# ZynqPower.net
KiCad netlist of a schematic drawn in Altium Designer
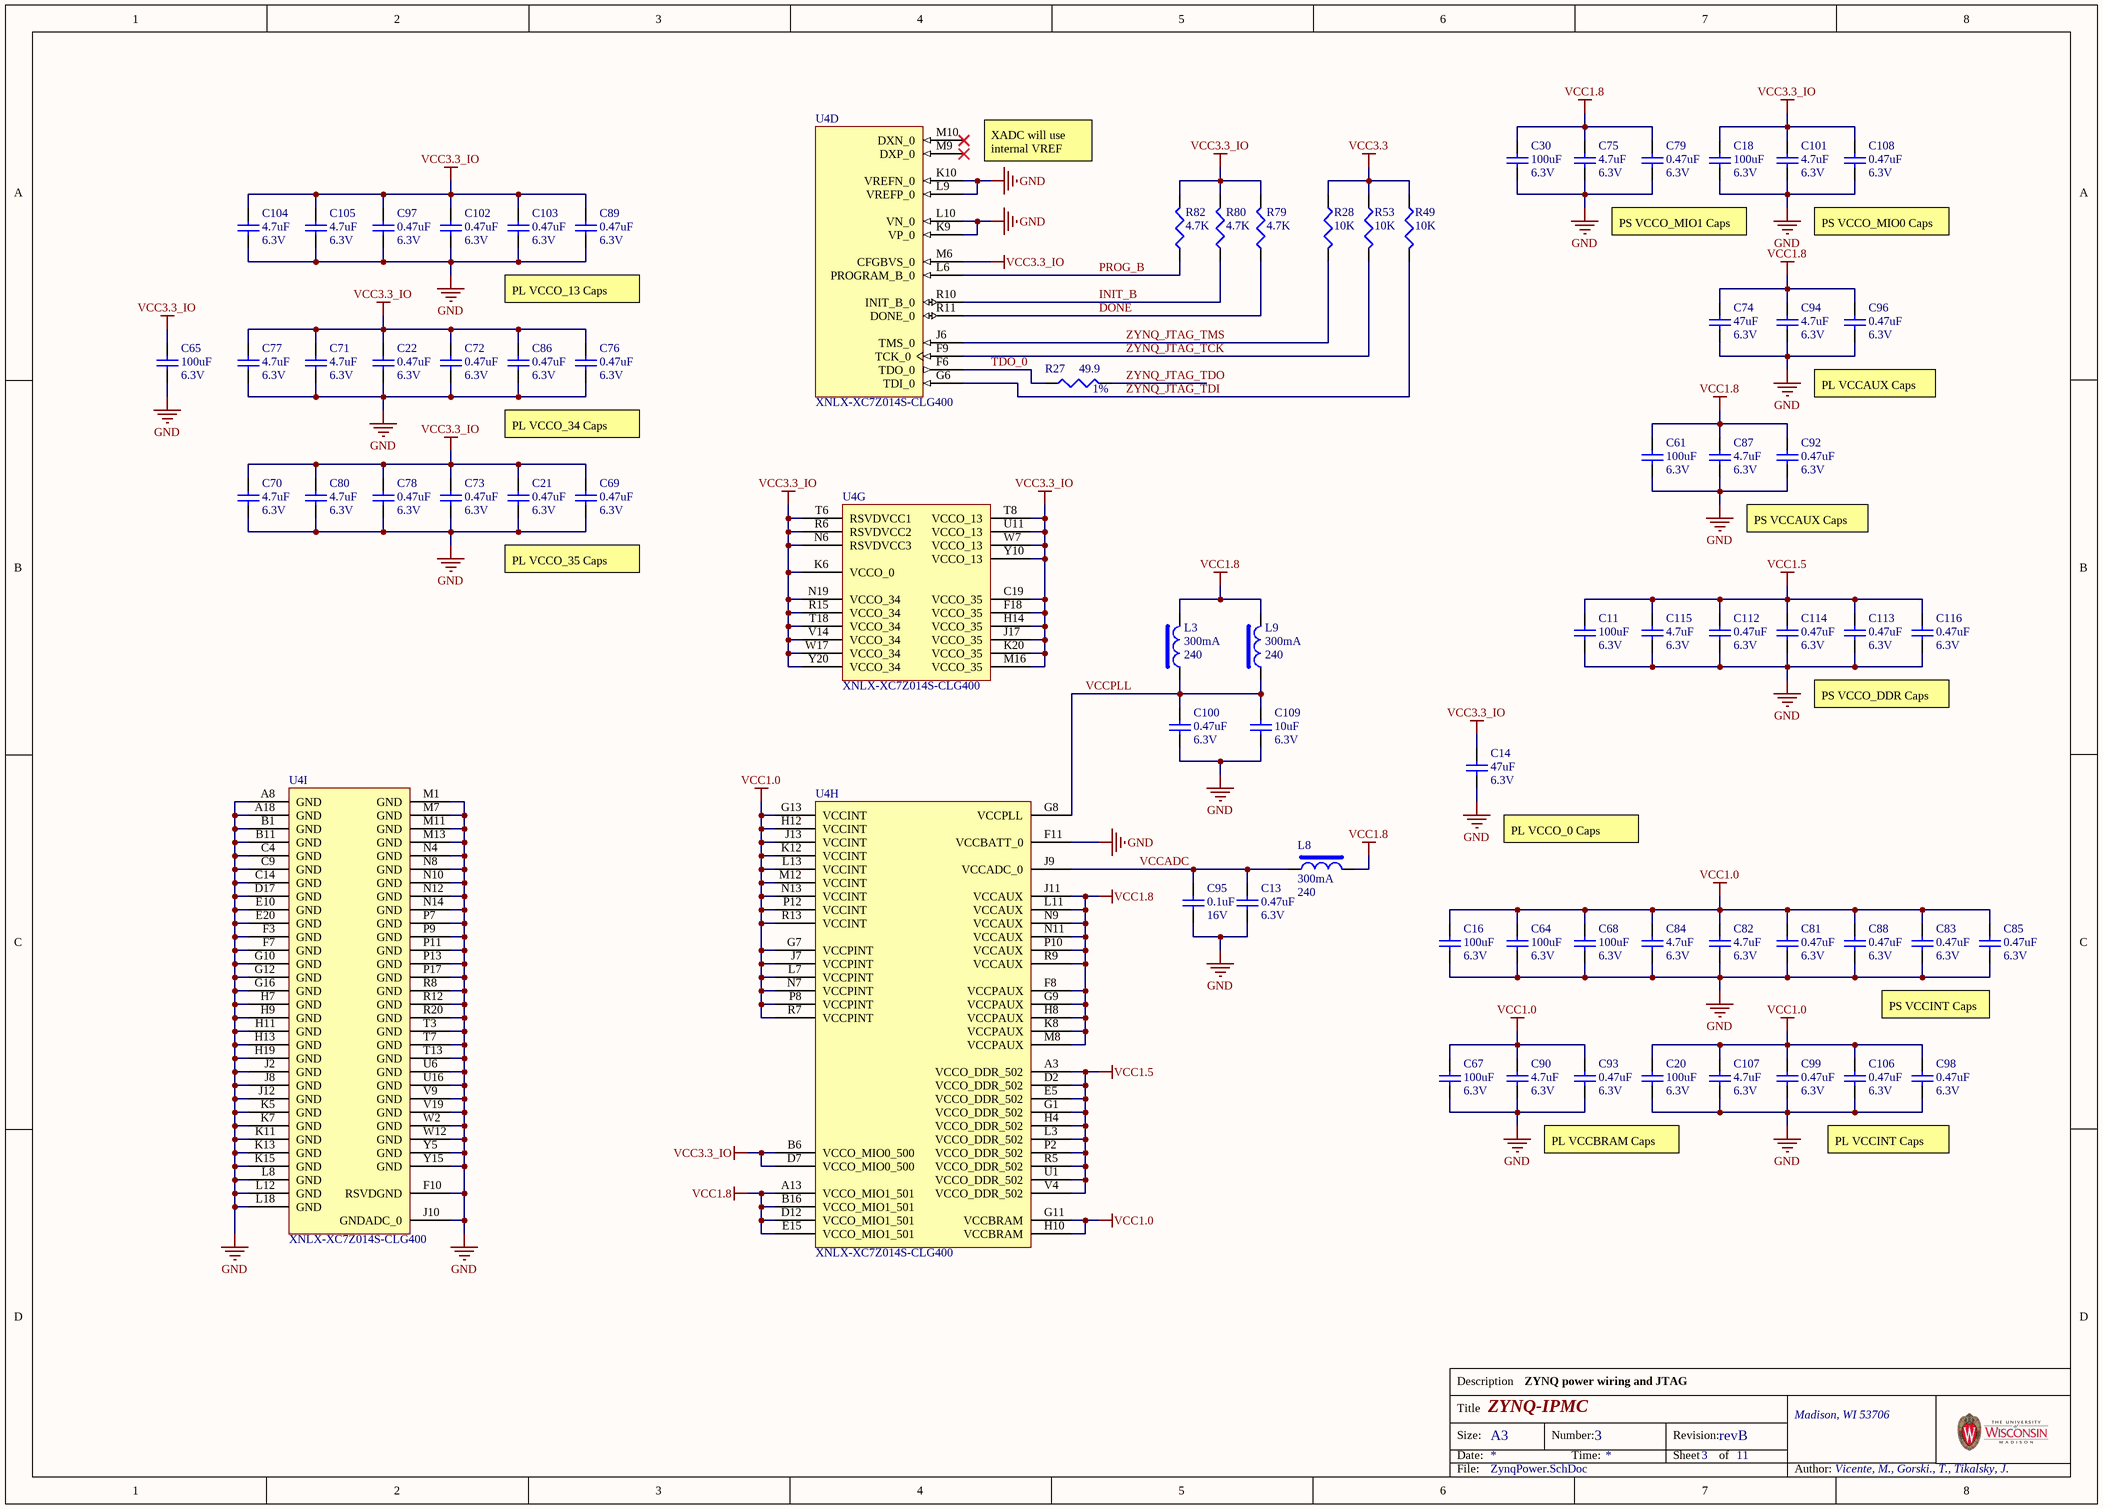
[diagram p0: ZynqPower.SchDoc]

(export (version "E")
  (design (tool "Eeschema 10.0.6"))
  (components
    (comp (ref "C11")
      (value "100uF")
      (footprint "C1210_IPC_H")
      (description "Capacitor")
      (fields
        (field (name "RATING") "6.3V")
        (field (name "PART") "GRM32ER60J107ME20L")
        (field (name "MANUFACTURER") "Murata")
      )
      (libsource (lib "CustomParts") (part "Cap"))
    )
    (comp (ref "C13")
      (value "0.47uF")
      (footprint "C0402_IPC_H")
      (description "Capacitor")
      (fields
        (field (name "RATING") "6.3V")
        (field (name "MANUFACTURER") "Murata")
        (field (name "PART") "GRM155R60J474KE19D")
      )
      (libsource (lib "CustomParts") (part "Cap"))
    )
    (comp (ref "C14")
      (value "47uF")
      (footprint "C0805_M")
      (description "Capacitor")
      (fields
        (field (name "RATING") "6.3V")
        (field (name "MANUFACTURER") "TDK")
        (field (name "PART") "C2012X5R0J476M125AC")
      )
      (libsource (lib "CustomParts") (part "Cap"))
    )
    (comp (ref "C16")
      (value "100uF")
      (footprint "C1210_IPC_H")
      (description "Capacitor")
      (fields
        (field (name "RATING") "6.3V")
        (field (name "PART") "GRM32ER60J107ME20L")
        (field (name "MANUFACTURER") "Murata")
      )
      (libsource (lib "CustomParts") (part "Cap"))
    )
    (comp (ref "C18")
      (value "100uF")
      (footprint "C1210_IPC_H")
      (description "Capacitor")
      (fields
        (field (name "RATING") "6.3V")
        (field (name "PART") "GRM32ER60J107ME20L")
        (field (name "MANUFACTURER") "Murata")
      )
      (libsource (lib "CustomParts") (part "Cap"))
    )
    (comp (ref "C20")
      (value "100uF")
      (footprint "C1210_IPC_H")
      (description "Capacitor")
      (fields
        (field (name "RATING") "6.3V")
        (field (name "PART") "GRM32ER60J107ME20L")
        (field (name "MANUFACTURER") "Murata")
      )
      (libsource (lib "CustomParts") (part "Cap"))
    )
    (comp (ref "C21")
      (value "0.47uF")
      (footprint "C0402_IPC_H")
      (description "Capacitor")
      (fields
        (field (name "RATING") "6.3V")
        (field (name "MANUFACTURER") "Murata")
        (field (name "PART") "GRM155R60J474KE19D")
      )
      (libsource (lib "CustomParts") (part "Cap"))
    )
    (comp (ref "C22")
      (value "0.47uF")
      (footprint "C0402_IPC_H")
      (description "Capacitor")
      (fields
        (field (name "RATING") "6.3V")
        (field (name "MANUFACTURER") "Murata")
        (field (name "PART") "GRM155R60J474KE19D")
      )
      (libsource (lib "CustomParts") (part "Cap"))
    )
    (comp (ref "C30")
      (value "100uF")
      (footprint "C1210_IPC_H")
      (description "Capacitor")
      (fields
        (field (name "RATING") "6.3V")
        (field (name "PART") "GRM32ER60J107ME20L")
        (field (name "MANUFACTURER") "Murata")
      )
      (libsource (lib "CustomParts") (part "Cap"))
    )
    (comp (ref "C61")
      (value "100uF")
      (footprint "C1210_IPC_H")
      (description "Capacitor")
      (fields
        (field (name "RATING") "6.3V")
        (field (name "PART") "GRM32ER60J107ME20L")
        (field (name "MANUFACTURER") "Murata")
      )
      (libsource (lib "CustomParts") (part "Cap"))
    )
    (comp (ref "C64")
      (value "100uF")
      (footprint "C1210_IPC_H")
      (description "Capacitor")
      (fields
        (field (name "RATING") "6.3V")
        (field (name "PART") "GRM32ER60J107ME20L")
        (field (name "MANUFACTURER") "Murata")
      )
      (libsource (lib "CustomParts") (part "Cap"))
    )
    (comp (ref "C65")
      (value "100uF")
      (footprint "C1210_IPC_H")
      (description "Capacitor")
      (fields
        (field (name "RATING") "6.3V")
        (field (name "PART") "GRM32ER60J107ME20L")
        (field (name "MANUFACTURER") "Murata")
      )
      (libsource (lib "CustomParts") (part "Cap"))
    )
    (comp (ref "C67")
      (value "100uF")
      (footprint "C1210_IPC_H")
      (description "Capacitor")
      (fields
        (field (name "RATING") "6.3V")
        (field (name "PART") "GRM32ER60J107ME20L")
        (field (name "MANUFACTURER") "Murata")
      )
      (libsource (lib "CustomParts") (part "Cap"))
    )
    (comp (ref "C68")
      (value "100uF")
      (footprint "C1210_IPC_H")
      (description "Capacitor")
      (fields
        (field (name "RATING") "6.3V")
        (field (name "PART") "GRM32ER60J107ME20L")
        (field (name "MANUFACTURER") "Murata")
      )
      (libsource (lib "CustomParts") (part "Cap"))
    )
    (comp (ref "C69")
      (value "0.47uF")
      (footprint "C0402_IPC_H")
      (description "Capacitor")
      (fields
        (field (name "RATING") "6.3V")
        (field (name "MANUFACTURER") "Murata")
        (field (name "PART") "GRM155R60J474KE19D")
      )
      (libsource (lib "CustomParts") (part "Cap"))
    )
    (comp (ref "C70")
      (value "4.7uF")
      (footprint "C0402_IPC_H")
      (description "Capacitor")
      (fields
        (field (name "RATING") "6.3V")
        (field (name "MANUFACTURER") "TDK")
        (field (name "PART") "C1005X5R0J475M050BC")
      )
      (libsource (lib "CustomParts") (part "Cap"))
    )
    (comp (ref "C71")
      (value "4.7uF")
      (footprint "C0402_IPC_H")
      (description "Capacitor")
      (fields
        (field (name "RATING") "6.3V")
        (field (name "MANUFACTURER") "TDK")
        (field (name "PART") "C1005X5R0J475M050BC")
      )
      (libsource (lib "CustomParts") (part "Cap"))
    )
    (comp (ref "C72")
      (value "0.47uF")
      (footprint "C0402_IPC_H")
      (description "Capacitor")
      (fields
        (field (name "RATING") "6.3V")
        (field (name "MANUFACTURER") "Murata")
        (field (name "PART") "GRM155R60J474KE19D")
      )
      (libsource (lib "CustomParts") (part "Cap"))
    )
    (comp (ref "C73")
      (value "0.47uF")
      (footprint "C0402_IPC_H")
      (description "Capacitor")
      (fields
        (field (name "RATING") "6.3V")
        (field (name "MANUFACTURER") "Murata")
        (field (name "PART") "GRM155R60J474KE19D")
      )
      (libsource (lib "CustomParts") (part "Cap"))
    )
    (comp (ref "C74")
      (value "47uF")
      (footprint "C0805_M")
      (description "Capacitor")
      (fields
        (field (name "RATING") "6.3V")
        (field (name "MANUFACTURER") "TDK")
        (field (name "PART") "C2012X5R0J476M125AC")
      )
      (libsource (lib "CustomParts") (part "Cap"))
    )
    (comp (ref "C75")
      (value "4.7uF")
      (footprint "C0402_IPC_H")
      (description "Capacitor")
      (fields
        (field (name "RATING") "6.3V")
        (field (name "MANUFACTURER") "TDK")
        (field (name "PART") "C1005X5R0J475M050BC")
      )
      (libsource (lib "CustomParts") (part "Cap"))
    )
    (comp (ref "C76")
      (value "0.47uF")
      (footprint "C0402_IPC_H")
      (description "Capacitor")
      (fields
        (field (name "RATING") "6.3V")
        (field (name "MANUFACTURER") "Murata")
        (field (name "PART") "GRM155R60J474KE19D")
      )
      (libsource (lib "CustomParts") (part "Cap"))
    )
    (comp (ref "C77")
      (value "4.7uF")
      (footprint "C0402_IPC_H")
      (description "Capacitor")
      (fields
        (field (name "RATING") "6.3V")
        (field (name "MANUFACTURER") "TDK")
        (field (name "PART") "C1005X5R0J475M050BC")
      )
      (libsource (lib "CustomParts") (part "Cap"))
    )
    (comp (ref "C78")
      (value "0.47uF")
      (footprint "C0402_IPC_H")
      (description "Capacitor")
      (fields
        (field (name "RATING") "6.3V")
        (field (name "MANUFACTURER") "Murata")
        (field (name "PART") "GRM155R60J474KE19D")
      )
      (libsource (lib "CustomParts") (part "Cap"))
    )
    (comp (ref "C79")
      (value "0.47uF")
      (footprint "C0402_IPC_H")
      (description "Capacitor")
      (fields
        (field (name "RATING") "6.3V")
        (field (name "MANUFACTURER") "Murata")
        (field (name "PART") "GRM155R60J474KE19D")
      )
      (libsource (lib "CustomParts") (part "Cap"))
    )
    (comp (ref "C80")
      (value "4.7uF")
      (footprint "C0402_IPC_H")
      (description "Capacitor")
      (fields
        (field (name "RATING") "6.3V")
        (field (name "MANUFACTURER") "TDK")
        (field (name "PART") "C1005X5R0J475M050BC")
      )
      (libsource (lib "CustomParts") (part "Cap"))
    )
    (comp (ref "C81")
      (value "0.47uF")
      (footprint "C0402_IPC_H")
      (description "Capacitor")
      (fields
        (field (name "RATING") "6.3V")
        (field (name "MANUFACTURER") "Murata")
        (field (name "PART") "GRM155R60J474KE19D")
      )
      (libsource (lib "CustomParts") (part "Cap"))
    )
    (comp (ref "C82")
      (value "4.7uF")
      (footprint "C0402_IPC_H")
      (description "Capacitor")
      (fields
        (field (name "RATING") "6.3V")
        (field (name "MANUFACTURER") "TDK")
        (field (name "PART") "C1005X5R0J475M050BC")
      )
      (libsource (lib "CustomParts") (part "Cap"))
    )
    (comp (ref "C83")
      (value "0.47uF")
      (footprint "C0402_IPC_H")
      (description "Capacitor")
      (fields
        (field (name "RATING") "6.3V")
        (field (name "MANUFACTURER") "Murata")
        (field (name "PART") "GRM155R60J474KE19D")
      )
      (libsource (lib "CustomParts") (part "Cap"))
    )
    (comp (ref "C84")
      (value "4.7uF")
      (footprint "C0402_IPC_H")
      (description "Capacitor")
      (fields
        (field (name "RATING") "6.3V")
        (field (name "MANUFACTURER") "TDK")
        (field (name "PART") "C1005X5R0J475M050BC")
      )
      (libsource (lib "CustomParts") (part "Cap"))
    )
    (comp (ref "C85")
      (value "0.47uF")
      (footprint "C0402_IPC_H")
      (description "Capacitor")
      (fields
        (field (name "RATING") "6.3V")
        (field (name "MANUFACTURER") "Murata")
        (field (name "PART") "GRM155R60J474KE19D")
      )
      (libsource (lib "CustomParts") (part "Cap"))
    )
    (comp (ref "C86")
      (value "0.47uF")
      (footprint "C0402_IPC_H")
      (description "Capacitor")
      (fields
        (field (name "RATING") "6.3V")
        (field (name "MANUFACTURER") "Murata")
        (field (name "PART") "GRM155R60J474KE19D")
      )
      (libsource (lib "CustomParts") (part "Cap"))
    )
    (comp (ref "C87")
      (value "4.7uF")
      (footprint "C0402_IPC_H")
      (description "Capacitor")
      (fields
        (field (name "RATING") "6.3V")
        (field (name "MANUFACTURER") "TDK")
        (field (name "PART") "C1005X5R0J475M050BC")
      )
      (libsource (lib "CustomParts") (part "Cap"))
    )
    (comp (ref "C88")
      (value "0.47uF")
      (footprint "C0402_IPC_H")
      (description "Capacitor")
      (fields
        (field (name "RATING") "6.3V")
        (field (name "MANUFACTURER") "Murata")
        (field (name "PART") "GRM155R60J474KE19D")
      )
      (libsource (lib "CustomParts") (part "Cap"))
    )
    (comp (ref "C89")
      (value "0.47uF")
      (footprint "C0402_IPC_H")
      (description "Capacitor")
      (fields
        (field (name "RATING") "6.3V")
        (field (name "MANUFACTURER") "Murata")
        (field (name "PART") "GRM155R60J474KE19D")
      )
      (libsource (lib "CustomParts") (part "Cap"))
    )
    (comp (ref "C90")
      (value "4.7uF")
      (footprint "C0402_IPC_H")
      (description "Capacitor")
      (fields
        (field (name "RATING") "6.3V")
        (field (name "MANUFACTURER") "TDK")
        (field (name "PART") "C1005X5R0J475M050BC")
      )
      (libsource (lib "CustomParts") (part "Cap"))
    )
    (comp (ref "C92")
      (value "0.47uF")
      (footprint "C0402_IPC_H")
      (description "Capacitor")
      (fields
        (field (name "RATING") "6.3V")
        (field (name "MANUFACTURER") "Murata")
        (field (name "PART") "GRM155R60J474KE19D")
      )
      (libsource (lib "CustomParts") (part "Cap"))
    )
    (comp (ref "C93")
      (value "0.47uF")
      (footprint "C0402_IPC_H")
      (description "Capacitor")
      (fields
        (field (name "RATING") "6.3V")
        (field (name "MANUFACTURER") "Murata")
        (field (name "PART") "GRM155R60J474KE19D")
      )
      (libsource (lib "CustomParts") (part "Cap"))
    )
    (comp (ref "C94")
      (value "4.7uF")
      (footprint "C0402_IPC_H")
      (description "Capacitor")
      (fields
        (field (name "RATING") "6.3V")
        (field (name "MANUFACTURER") "TDK")
        (field (name "PART") "C1005X5R0J475M050BC")
      )
      (libsource (lib "CustomParts") (part "Cap"))
    )
    (comp (ref "C95")
      (value "0.1uF")
      (footprint "C0402_IPC_H")
      (description "Capacitor")
      (fields
        (field (name "RATING") "16V")
        (field (name "MANUFACTURER") "Murata")
        (field (name "PART") "GRM155R71C104KA88D")
      )
      (libsource (lib "CustomParts") (part "Cap"))
    )
    (comp (ref "C96")
      (value "0.47uF")
      (footprint "C0402_IPC_H")
      (description "Capacitor")
      (fields
        (field (name "RATING") "6.3V")
        (field (name "MANUFACTURER") "Murata")
        (field (name "PART") "GRM155R60J474KE19D")
      )
      (libsource (lib "CustomParts") (part "Cap"))
    )
    (comp (ref "C97")
      (value "0.47uF")
      (footprint "C0402_IPC_H")
      (description "Capacitor")
      (fields
        (field (name "RATING") "6.3V")
        (field (name "MANUFACTURER") "Murata")
        (field (name "PART") "GRM155R60J474KE19D")
      )
      (libsource (lib "CustomParts") (part "Cap"))
    )
    (comp (ref "C98")
      (value "0.47uF")
      (footprint "C0402_IPC_H")
      (description "Capacitor")
      (fields
        (field (name "RATING") "6.3V")
        (field (name "MANUFACTURER") "Murata")
        (field (name "PART") "GRM155R60J474KE19D")
      )
      (libsource (lib "CustomParts") (part "Cap"))
    )
    (comp (ref "C99")
      (value "0.47uF")
      (footprint "C0402_IPC_H")
      (description "Capacitor")
      (fields
        (field (name "RATING") "6.3V")
        (field (name "MANUFACTURER") "Murata")
        (field (name "PART") "GRM155R60J474KE19D")
      )
      (libsource (lib "CustomParts") (part "Cap"))
    )
    (comp (ref "C100")
      (value "0.47uF")
      (footprint "C0402_IPC_H")
      (description "Capacitor")
      (fields
        (field (name "RATING") "6.3V")
        (field (name "MANUFACTURER") "Murata")
        (field (name "PART") "GRM155R60J474KE19D")
      )
      (libsource (lib "CustomParts") (part "Cap"))
    )
    (comp (ref "C101")
      (value "4.7uF")
      (footprint "C0402_IPC_H")
      (description "Capacitor")
      (fields
        (field (name "RATING") "6.3V")
        (field (name "MANUFACTURER") "TDK")
        (field (name "PART") "C1005X5R0J475M050BC")
      )
      (libsource (lib "CustomParts") (part "Cap"))
    )
    (comp (ref "C102")
      (value "0.47uF")
      (footprint "C0402_IPC_H")
      (description "Capacitor")
      (fields
        (field (name "RATING") "6.3V")
        (field (name "MANUFACTURER") "Murata")
        (field (name "PART") "GRM155R60J474KE19D")
      )
      (libsource (lib "CustomParts") (part "Cap"))
    )
    (comp (ref "C103")
      (value "0.47uF")
      (footprint "C0402_IPC_H")
      (description "Capacitor")
      (fields
        (field (name "RATING") "6.3V")
        (field (name "MANUFACTURER") "Murata")
        (field (name "PART") "GRM155R60J474KE19D")
      )
      (libsource (lib "CustomParts") (part "Cap"))
    )
    (comp (ref "C104")
      (value "4.7uF")
      (footprint "C0402_IPC_H")
      (description "Capacitor")
      (fields
        (field (name "RATING") "6.3V")
        (field (name "MANUFACTURER") "TDK")
        (field (name "PART") "C1005X5R0J475M050BC")
      )
      (libsource (lib "CustomParts") (part "Cap"))
    )
    (comp (ref "C105")
      (value "4.7uF")
      (footprint "C0402_IPC_H")
      (description "Capacitor")
      (fields
        (field (name "RATING") "6.3V")
        (field (name "MANUFACTURER") "TDK")
        (field (name "PART") "C1005X5R0J475M050BC")
      )
      (libsource (lib "CustomParts") (part "Cap"))
    )
    (comp (ref "C106")
      (value "0.47uF")
      (footprint "C0402_IPC_H")
      (description "Capacitor")
      (fields
        (field (name "RATING") "6.3V")
        (field (name "MANUFACTURER") "Murata")
        (field (name "PART") "GRM155R60J474KE19D")
      )
      (libsource (lib "CustomParts") (part "Cap"))
    )
    (comp (ref "C107")
      (value "4.7uF")
      (footprint "C0402_IPC_H")
      (description "Capacitor")
      (fields
        (field (name "RATING") "6.3V")
        (field (name "MANUFACTURER") "TDK")
        (field (name "PART") "C1005X5R0J475M050BC")
      )
      (libsource (lib "CustomParts") (part "Cap"))
    )
    (comp (ref "C108")
      (value "0.47uF")
      (footprint "C0402_IPC_H")
      (description "Capacitor")
      (fields
        (field (name "RATING") "6.3V")
        (field (name "MANUFACTURER") "Murata")
        (field (name "PART") "GRM155R60J474KE19D")
      )
      (libsource (lib "CustomParts") (part "Cap"))
    )
    (comp (ref "C109")
      (value "10uF")
      (footprint "C0402_IPC_H")
      (description "Capacitor")
      (fields
        (field (name "RATING") "6.3V")
        (field (name "MANUFACTURER") "Murata")
        (field (name "PART") "GRM155R60J106ME44D")
      )
      (libsource (lib "CustomParts") (part "Cap"))
    )
    (comp (ref "C112")
      (value "0.47uF")
      (footprint "C0402_IPC_H")
      (description "Capacitor")
      (fields
        (field (name "RATING") "6.3V")
        (field (name "MANUFACTURER") "Murata")
        (field (name "PART") "GRM155R60J474KE19D")
      )
      (libsource (lib "CustomParts") (part "Cap"))
    )
    (comp (ref "C113")
      (value "0.47uF")
      (footprint "C0402_IPC_H")
      (description "Capacitor")
      (fields
        (field (name "RATING") "6.3V")
        (field (name "MANUFACTURER") "Murata")
        (field (name "PART") "GRM155R60J474KE19D")
      )
      (libsource (lib "CustomParts") (part "Cap"))
    )
    (comp (ref "C114")
      (value "0.47uF")
      (footprint "C0402_IPC_H")
      (description "Capacitor")
      (fields
        (field (name "RATING") "6.3V")
        (field (name "MANUFACTURER") "Murata")
        (field (name "PART") "GRM155R60J474KE19D")
      )
      (libsource (lib "CustomParts") (part "Cap"))
    )
    (comp (ref "C115")
      (value "4.7uF")
      (footprint "C0402_IPC_H")
      (description "Capacitor")
      (fields
        (field (name "RATING") "6.3V")
        (field (name "MANUFACTURER") "TDK")
        (field (name "PART") "C1005X5R0J475M050BC")
      )
      (libsource (lib "CustomParts") (part "Cap"))
    )
    (comp (ref "C116")
      (value "0.47uF")
      (footprint "C0402_IPC_H")
      (description "Capacitor")
      (fields
        (field (name "RATING") "6.3V")
        (field (name "MANUFACTURER") "Murata")
        (field (name "PART") "GRM155R60J474KE19D")
      )
      (libsource (lib "CustomParts") (part "Cap"))
    )
    (comp (ref "L3")
      (value "240")
      (footprint "L0402_H")
      (description "Bead Inductor")
      (fields
        (field (name "RATED CURRENT") "300mA")
        (field (name "MANUFACTURER") "Taiyo Yuden")
        (field (name "PART") "BK1005HM241-T")
      )
      (libsource (lib "CustomParts") (part "Bead"))
    )
    (comp (ref "L8")
      (value "240")
      (footprint "L0402_H")
      (description "Bead Inductor")
      (fields
        (field (name "RATED CURRENT") "300mA")
        (field (name "MANUFACTURER") "Taiyo Yuden")
        (field (name "PART") "BK1005HM241-T")
      )
      (libsource (lib "CustomParts") (part "Bead"))
    )
    (comp (ref "L9")
      (value "240")
      (footprint "L0402_H")
      (description "Bead Inductor")
      (fields
        (field (name "RATED CURRENT") "300mA")
        (field (name "MANUFACTURER") "Taiyo Yuden")
        (field (name "PART") "BK1005HM241-T")
      )
      (libsource (lib "CustomParts") (part "Bead"))
    )
    (comp (ref "R27")
      (value "49.9")
      (footprint "R0402_IPC_H")
      (description "Resistor")
      (fields
        (field (name "TOLERANCE") "1%")
        (field (name "MANUFACTURER") "Panasonic")
        (field (name "PART") "ERJ-2RKF49R9X")
      )
      (libsource (lib "CustomParts") (part "Res"))
    )
    (comp (ref "R28")
      (value "10K")
      (footprint "R0402_IPC_H")
      (description "Resistor")
      (fields (field (name "TOLERANCE") "5%") (field (name "MANUFACTURER") "Panasonic-ECG"))
      (libsource (lib "CustomParts") (part "Res"))
    )
    (comp (ref "R49")
      (value "10K")
      (footprint "R0402_IPC_H")
      (description "Resistor")
      (fields (field (name "TOLERANCE") "5%") (field (name "MANUFACTURER") "Panasonic-ECG"))
      (libsource (lib "CustomParts") (part "Res"))
    )
    (comp (ref "R53")
      (value "10K")
      (footprint "R0402_IPC_H")
      (description "Resistor")
      (fields (field (name "TOLERANCE") "5%") (field (name "MANUFACTURER") "Panasonic-ECG"))
      (libsource (lib "CustomParts") (part "Res"))
    )
    (comp (ref "R79")
      (value "4.7K")
      (footprint "R0402_IPC_H")
      (description "Resistor")
      (fields (field (name "TOLERANCE") "1%") (field (name "MANUFACTURER") "Panasonic"))
      (libsource (lib "CustomParts") (part "Res"))
    )
    (comp (ref "R80")
      (value "4.7K")
      (footprint "R0402_IPC_H")
      (description "Resistor")
      (fields (field (name "TOLERANCE") "1%") (field (name "MANUFACTURER") "Panasonic"))
      (libsource (lib "CustomParts") (part "Res"))
    )
    (comp (ref "R82")
      (value "4.7K")
      (footprint "R0402_IPC_H")
      (description "Resistor")
      (fields (field (name "TOLERANCE") "1%") (field (name "MANUFACTURER") "Panasonic"))
      (libsource (lib "CustomParts") (part "Res"))
    )
    (comp (ref "U4")
      (value "XNLX-XC7Z014S-CLG400")
      (footprint "CLG400")
      (fields (field (name "MANUFACTURER") "Xilinx") (field (name "PART") "XC7Z014S-1CLG400C"))
      (libsource (lib "") (part "XNLX-XC7Z020-CLG400_1"))
    )
  )
  (nets
    (net (code "1") (name "/DONE") (class "Default")
      (node (ref "R79") (pin "1") (pinfunction "1_1") (pintype "passive"))
      (node (ref "U4") (pin "R11") (pinfunction "DONE_0_R11") (pintype "bidirectional"))
    )
    (net (code "2") (name "/INIT_B") (class "Default")
      (node (ref "R80") (pin "1") (pinfunction "1_1") (pintype "passive"))
      (node (ref "U4") (pin "R10") (pinfunction "INIT_B_0_R10") (pintype "bidirectional"))
    )
    (net (code "3") (name "/PROG_B") (class "Default")
      (node (ref "R82") (pin "1") (pinfunction "1_1") (pintype "passive"))
      (node (ref "U4") (pin "L6") (pinfunction "PROGRAM_B_0_L6") (pintype "input"))
    )
    (net (code "4") (name "/TDO_0") (class "Default")
      (node (ref "R27") (pin "2") (pinfunction "2_2") (pintype "passive"))
      (node (ref "U4") (pin "F6") (pinfunction "TDO_0_F6") (pintype "output"))
    )
    (net (code "5") (name "/VCCADC") (class "Default")
      (node (ref "C13") (pin "1") (pinfunction "1_1") (pintype "passive"))
      (node (ref "C95") (pin "1") (pinfunction "1_1") (pintype "passive"))
      (node (ref "L8") (pin "1") (pinfunction "1_1") (pintype "passive"))
      (node (ref "U4") (pin "J9") (pinfunction "VCCADC_0_J9") (pintype "power_in"))
    )
    (net (code "6") (name "/VCCPLL") (class "Default")
      (node (ref "C100") (pin "1") (pinfunction "1_1") (pintype "passive"))
      (node (ref "C109") (pin "1") (pinfunction "1_1") (pintype "passive"))
      (node (ref "L3") (pin "1") (pinfunction "1_1") (pintype "passive"))
      (node (ref "L9") (pin "1") (pinfunction "1_1") (pintype "passive"))
      (node (ref "U4") (pin "G8") (pinfunction "VCCPLL_G8") (pintype "power_in"))
    )
    (net (code "7") (name "/ZYNQ_JTAG_TCK") (class "Default")
      (node (ref "R53") (pin "2") (pinfunction "2_2") (pintype "passive"))
      (node (ref "U4") (pin "F9") (pinfunction "TCK_0_F9") (pintype "input"))
    )
    (net (code "8") (name "/ZYNQ_JTAG_TDI") (class "Default")
      (node (ref "R49") (pin "2") (pinfunction "2_2") (pintype "passive"))
      (node (ref "U4") (pin "G6") (pinfunction "TDI_0_G6") (pintype "input"))
    )
    (net (code "9") (name "/ZYNQ_JTAG_TDO") (class "Default")
      (node (ref "R27") (pin "1") (pinfunction "1_1") (pintype "passive"))
    )
    (net (code "10") (name "/ZYNQ_JTAG_TMS") (class "Default")
      (node (ref "R28") (pin "2") (pinfunction "2_2") (pintype "passive"))
      (node (ref "U4") (pin "J6") (pinfunction "TMS_0_J6") (pintype "input"))
    )
    (net (code "11") (name "GND") (class "Default")
      (node (ref "C100") (pin "2") (pinfunction "2_2") (pintype "passive"))
      (node (ref "C101") (pin "2") (pinfunction "2_2") (pintype "passive"))
      (node (ref "C102") (pin "2") (pinfunction "2_2") (pintype "passive"))
      (node (ref "C103") (pin "2") (pinfunction "2_2") (pintype "passive"))
      (node (ref "C104") (pin "2") (pinfunction "2_2") (pintype "passive"))
      (node (ref "C105") (pin "2") (pinfunction "2_2") (pintype "passive"))
      (node (ref "C106") (pin "2") (pinfunction "2_2") (pintype "passive"))
      (node (ref "C107") (pin "2") (pinfunction "2_2") (pintype "passive"))
      (node (ref "C108") (pin "2") (pinfunction "2_2") (pintype "passive"))
      (node (ref "C109") (pin "2") (pinfunction "2_2") (pintype "passive"))
      (node (ref "C11") (pin "2") (pinfunction "2_2") (pintype "passive"))
      (node (ref "C112") (pin "2") (pinfunction "2_2") (pintype "passive"))
      (node (ref "C113") (pin "2") (pinfunction "2_2") (pintype "passive"))
      (node (ref "C114") (pin "2") (pinfunction "2_2") (pintype "passive"))
      (node (ref "C115") (pin "2") (pinfunction "2_2") (pintype "passive"))
      (node (ref "C116") (pin "2") (pinfunction "2_2") (pintype "passive"))
      (node (ref "C13") (pin "2") (pinfunction "2_2") (pintype "passive"))
      (node (ref "C14") (pin "2") (pinfunction "2_2") (pintype "passive"))
      (node (ref "C16") (pin "2") (pinfunction "2_2") (pintype "passive"))
      (node (ref "C18") (pin "2") (pinfunction "2_2") (pintype "passive"))
      (node (ref "C20") (pin "2") (pinfunction "2_2") (pintype "passive"))
      (node (ref "C21") (pin "2") (pinfunction "2_2") (pintype "passive"))
      (node (ref "C22") (pin "2") (pinfunction "2_2") (pintype "passive"))
      (node (ref "C30") (pin "2") (pinfunction "2_2") (pintype "passive"))
      (node (ref "C61") (pin "2") (pinfunction "2_2") (pintype "passive"))
      (node (ref "C64") (pin "2") (pinfunction "2_2") (pintype "passive"))
      (node (ref "C65") (pin "2") (pinfunction "2_2") (pintype "passive"))
      (node (ref "C67") (pin "2") (pinfunction "2_2") (pintype "passive"))
      (node (ref "C68") (pin "2") (pinfunction "2_2") (pintype "passive"))
      (node (ref "C69") (pin "2") (pinfunction "2_2") (pintype "passive"))
      (node (ref "C70") (pin "2") (pinfunction "2_2") (pintype "passive"))
      (node (ref "C71") (pin "2") (pinfunction "2_2") (pintype "passive"))
      (node (ref "C72") (pin "2") (pinfunction "2_2") (pintype "passive"))
      (node (ref "C73") (pin "2") (pinfunction "2_2") (pintype "passive"))
      (node (ref "C74") (pin "2") (pinfunction "2_2") (pintype "passive"))
      (node (ref "C75") (pin "2") (pinfunction "2_2") (pintype "passive"))
      (node (ref "C76") (pin "2") (pinfunction "2_2") (pintype "passive"))
      (node (ref "C77") (pin "2") (pinfunction "2_2") (pintype "passive"))
      (node (ref "C78") (pin "2") (pinfunction "2_2") (pintype "passive"))
      (node (ref "C79") (pin "2") (pinfunction "2_2") (pintype "passive"))
      (node (ref "C80") (pin "2") (pinfunction "2_2") (pintype "passive"))
      (node (ref "C81") (pin "2") (pinfunction "2_2") (pintype "passive"))
      (node (ref "C82") (pin "2") (pinfunction "2_2") (pintype "passive"))
      (node (ref "C83") (pin "2") (pinfunction "2_2") (pintype "passive"))
      (node (ref "C84") (pin "2") (pinfunction "2_2") (pintype "passive"))
      (node (ref "C85") (pin "2") (pinfunction "2_2") (pintype "passive"))
      (node (ref "C86") (pin "2") (pinfunction "2_2") (pintype "passive"))
      (node (ref "C87") (pin "2") (pinfunction "2_2") (pintype "passive"))
      (node (ref "C88") (pin "2") (pinfunction "2_2") (pintype "passive"))
      (node (ref "C89") (pin "2") (pinfunction "2_2") (pintype "passive"))
      (node (ref "C90") (pin "2") (pinfunction "2_2") (pintype "passive"))
      (node (ref "C92") (pin "2") (pinfunction "2_2") (pintype "passive"))
      (node (ref "C93") (pin "2") (pinfunction "2_2") (pintype "passive"))
      (node (ref "C94") (pin "2") (pinfunction "2_2") (pintype "passive"))
      (node (ref "C95") (pin "2") (pinfunction "2_2") (pintype "passive"))
      (node (ref "C96") (pin "2") (pinfunction "2_2") (pintype "passive"))
      (node (ref "C97") (pin "2") (pinfunction "2_2") (pintype "passive"))
      (node (ref "C98") (pin "2") (pinfunction "2_2") (pintype "passive"))
      (node (ref "C99") (pin "2") (pinfunction "2_2") (pintype "passive"))
      (node (ref "U4") (pin "A18") (pinfunction "GND_A18") (pintype "power_in"))
      (node (ref "U4") (pin "A8") (pinfunction "GND_A8") (pintype "power_in"))
      (node (ref "U4") (pin "B1") (pinfunction "GND_B1") (pintype "power_in"))
      (node (ref "U4") (pin "B11") (pinfunction "GND_B11") (pintype "power_in"))
      (node (ref "U4") (pin "C14") (pinfunction "GND_C14") (pintype "power_in"))
      (node (ref "U4") (pin "C4") (pinfunction "GND_C4") (pintype "power_in"))
      (node (ref "U4") (pin "C9") (pinfunction "GND_C9") (pintype "power_in"))
      (node (ref "U4") (pin "D17") (pinfunction "GND_D17") (pintype "power_in"))
      (node (ref "U4") (pin "E10") (pinfunction "GND_E10") (pintype "power_in"))
      (node (ref "U4") (pin "E20") (pinfunction "GND_E20") (pintype "power_in"))
      (node (ref "U4") (pin "F10") (pinfunction "RSVDGND_F10") (pintype "power_in"))
      (node (ref "U4") (pin "F11") (pinfunction "VCCBATT_0_F11") (pintype "power_in"))
      (node (ref "U4") (pin "F3") (pinfunction "GND_F3") (pintype "power_in"))
      (node (ref "U4") (pin "F7") (pinfunction "GND_F7") (pintype "power_in"))
      (node (ref "U4") (pin "G10") (pinfunction "GND_G10") (pintype "power_in"))
      (node (ref "U4") (pin "G12") (pinfunction "GND_G12") (pintype "power_in"))
      (node (ref "U4") (pin "G16") (pinfunction "GND_G16") (pintype "power_in"))
      (node (ref "U4") (pin "H11") (pinfunction "GND_H11") (pintype "power_in"))
      (node (ref "U4") (pin "H13") (pinfunction "GND_H13") (pintype "power_in"))
      (node (ref "U4") (pin "H19") (pinfunction "GND_H19") (pintype "power_in"))
      (node (ref "U4") (pin "H7") (pinfunction "GND_H7") (pintype "power_in"))
      (node (ref "U4") (pin "H9") (pinfunction "GND_H9") (pintype "power_in"))
      (node (ref "U4") (pin "J10") (pinfunction "GNDADC_0_J10") (pintype "power_in"))
      (node (ref "U4") (pin "J12") (pinfunction "GND_J12") (pintype "power_in"))
      (node (ref "U4") (pin "J2") (pinfunction "GND_J2") (pintype "power_in"))
      (node (ref "U4") (pin "J8") (pinfunction "GND_J8") (pintype "power_in"))
      (node (ref "U4") (pin "K10") (pinfunction "VREFN_0_K10") (pintype "input"))
      (node (ref "U4") (pin "K11") (pinfunction "GND_K11") (pintype "power_in"))
      (node (ref "U4") (pin "K13") (pinfunction "GND_K13") (pintype "power_in"))
      (node (ref "U4") (pin "K15") (pinfunction "GND_K15") (pintype "power_in"))
      (node (ref "U4") (pin "K5") (pinfunction "GND_K5") (pintype "power_in"))
      (node (ref "U4") (pin "K7") (pinfunction "GND_K7") (pintype "power_in"))
      (node (ref "U4") (pin "K9") (pinfunction "VP_0_K9") (pintype "input"))
      (node (ref "U4") (pin "L10") (pinfunction "VN_0_L10") (pintype "input"))
      (node (ref "U4") (pin "L12") (pinfunction "GND_L12") (pintype "power_in"))
      (node (ref "U4") (pin "L18") (pinfunction "GND_L18") (pintype "power_in"))
      (node (ref "U4") (pin "L8") (pinfunction "GND_L8") (pintype "power_in"))
      (node (ref "U4") (pin "L9") (pinfunction "VREFP_0_L9") (pintype "input"))
      (node (ref "U4") (pin "M1") (pinfunction "GND_M1") (pintype "power_in"))
      (node (ref "U4") (pin "M11") (pinfunction "GND_M11") (pintype "power_in"))
      (node (ref "U4") (pin "M13") (pinfunction "GND_M13") (pintype "power_in"))
      (node (ref "U4") (pin "M7") (pinfunction "GND_M7") (pintype "power_in"))
      (node (ref "U4") (pin "N10") (pinfunction "GND_N10") (pintype "power_in"))
      (node (ref "U4") (pin "N12") (pinfunction "GND_N12") (pintype "power_in"))
      (node (ref "U4") (pin "N14") (pinfunction "GND_N14") (pintype "power_in"))
      (node (ref "U4") (pin "N4") (pinfunction "GND_N4") (pintype "power_in"))
      (node (ref "U4") (pin "N8") (pinfunction "GND_N8") (pintype "power_in"))
      (node (ref "U4") (pin "P11") (pinfunction "GND_P11") (pintype "power_in"))
      (node (ref "U4") (pin "P13") (pinfunction "GND_P13") (pintype "power_in"))
      (node (ref "U4") (pin "P17") (pinfunction "GND_P17") (pintype "power_in"))
      (node (ref "U4") (pin "P7") (pinfunction "GND_P7") (pintype "power_in"))
      (node (ref "U4") (pin "P9") (pinfunction "GND_P9") (pintype "power_in"))
      (node (ref "U4") (pin "R12") (pinfunction "GND_R12") (pintype "power_in"))
      (node (ref "U4") (pin "R20") (pinfunction "GND_R20") (pintype "power_in"))
      (node (ref "U4") (pin "R8") (pinfunction "GND_R8") (pintype "power_in"))
      (node (ref "U4") (pin "T13") (pinfunction "GND_T13") (pintype "power_in"))
      (node (ref "U4") (pin "T3") (pinfunction "GND_T3") (pintype "power_in"))
      (node (ref "U4") (pin "T7") (pinfunction "GND_T7") (pintype "power_in"))
      (node (ref "U4") (pin "U16") (pinfunction "GND_U16") (pintype "power_in"))
      (node (ref "U4") (pin "U6") (pinfunction "GND_U6") (pintype "power_in"))
      (node (ref "U4") (pin "V19") (pinfunction "GND_V19") (pintype "power_in"))
      (node (ref "U4") (pin "V9") (pinfunction "GND_V9") (pintype "power_in"))
      (node (ref "U4") (pin "W12") (pinfunction "GND_W12") (pintype "power_in"))
      (node (ref "U4") (pin "W2") (pinfunction "GND_W2") (pintype "power_in"))
      (node (ref "U4") (pin "Y15") (pinfunction "GND_Y15") (pintype "power_in"))
      (node (ref "U4") (pin "Y5") (pinfunction "GND_Y5") (pintype "power_in"))
    )
    (net (code "12") (name "VCC1.0") (class "Default")
      (node (ref "C106") (pin "1") (pinfunction "1_1") (pintype "passive"))
      (node (ref "C107") (pin "1") (pinfunction "1_1") (pintype "passive"))
      (node (ref "C16") (pin "1") (pinfunction "1_1") (pintype "passive"))
      (node (ref "C20") (pin "1") (pinfunction "1_1") (pintype "passive"))
      (node (ref "C64") (pin "1") (pinfunction "1_1") (pintype "passive"))
      (node (ref "C67") (pin "1") (pinfunction "1_1") (pintype "passive"))
      (node (ref "C68") (pin "1") (pinfunction "1_1") (pintype "passive"))
      (node (ref "C81") (pin "1") (pinfunction "1_1") (pintype "passive"))
      (node (ref "C82") (pin "1") (pinfunction "1_1") (pintype "passive"))
      (node (ref "C83") (pin "1") (pinfunction "1_1") (pintype "passive"))
      (node (ref "C84") (pin "1") (pinfunction "1_1") (pintype "passive"))
      (node (ref "C85") (pin "1") (pinfunction "1_1") (pintype "passive"))
      (node (ref "C88") (pin "1") (pinfunction "1_1") (pintype "passive"))
      (node (ref "C90") (pin "1") (pinfunction "1_1") (pintype "passive"))
      (node (ref "C93") (pin "1") (pinfunction "1_1") (pintype "passive"))
      (node (ref "C98") (pin "1") (pinfunction "1_1") (pintype "passive"))
      (node (ref "C99") (pin "1") (pinfunction "1_1") (pintype "passive"))
      (node (ref "U4") (pin "G11") (pinfunction "VCCBRAM_G11") (pintype "power_in"))
      (node (ref "U4") (pin "G13") (pinfunction "VCCINT_G13") (pintype "power_in"))
      (node (ref "U4") (pin "G7") (pinfunction "VCCPINT_G7") (pintype "power_in"))
      (node (ref "U4") (pin "H10") (pinfunction "VCCBRAM_H10") (pintype "power_in"))
      (node (ref "U4") (pin "H12") (pinfunction "VCCINT_H12") (pintype "power_in"))
      (node (ref "U4") (pin "J13") (pinfunction "VCCINT_J13") (pintype "power_in"))
      (node (ref "U4") (pin "J7") (pinfunction "VCCPINT_J7") (pintype "power_in"))
      (node (ref "U4") (pin "K12") (pinfunction "VCCINT_K12") (pintype "power_in"))
      (node (ref "U4") (pin "L13") (pinfunction "VCCINT_L13") (pintype "power_in"))
      (node (ref "U4") (pin "L7") (pinfunction "VCCPINT_L7") (pintype "power_in"))
      (node (ref "U4") (pin "M12") (pinfunction "VCCINT_M12") (pintype "power_in"))
      (node (ref "U4") (pin "N13") (pinfunction "VCCINT_N13") (pintype "power_in"))
      (node (ref "U4") (pin "N7") (pinfunction "VCCPINT_N7") (pintype "power_in"))
      (node (ref "U4") (pin "P12") (pinfunction "VCCINT_P12") (pintype "power_in"))
      (node (ref "U4") (pin "P8") (pinfunction "VCCPINT_P8") (pintype "power_in"))
      (node (ref "U4") (pin "R13") (pinfunction "VCCINT_R13") (pintype "power_in"))
      (node (ref "U4") (pin "R7") (pinfunction "VCCPINT_R7") (pintype "power_in"))
    )
    (net (code "13") (name "VCC1.5") (class "Default")
      (node (ref "C11") (pin "1") (pinfunction "1_1") (pintype "passive"))
      (node (ref "C112") (pin "1") (pinfunction "1_1") (pintype "passive"))
      (node (ref "C113") (pin "1") (pinfunction "1_1") (pintype "passive"))
      (node (ref "C114") (pin "1") (pinfunction "1_1") (pintype "passive"))
      (node (ref "C115") (pin "1") (pinfunction "1_1") (pintype "passive"))
      (node (ref "C116") (pin "1") (pinfunction "1_1") (pintype "passive"))
      (node (ref "U4") (pin "A3") (pinfunction "VCCO_DDR_502_A3") (pintype "power_in"))
      (node (ref "U4") (pin "D2") (pinfunction "VCCO_DDR_502_D2") (pintype "power_in"))
      (node (ref "U4") (pin "E5") (pinfunction "VCCO_DDR_502_E5") (pintype "power_in"))
      (node (ref "U4") (pin "G1") (pinfunction "VCCO_DDR_502_G1") (pintype "power_in"))
      (node (ref "U4") (pin "H4") (pinfunction "VCCO_DDR_502_H4") (pintype "power_in"))
      (node (ref "U4") (pin "L3") (pinfunction "VCCO_DDR_502_L3") (pintype "power_in"))
      (node (ref "U4") (pin "P2") (pinfunction "VCCO_DDR_502_P2") (pintype "power_in"))
      (node (ref "U4") (pin "R5") (pinfunction "VCCO_DDR_502_R5") (pintype "power_in"))
      (node (ref "U4") (pin "U1") (pinfunction "VCCO_DDR_502_U1") (pintype "power_in"))
      (node (ref "U4") (pin "V4") (pinfunction "VCCO_DDR_502_V4") (pintype "power_in"))
    )
    (net (code "14") (name "VCC1.8") (class "Default")
      (node (ref "C30") (pin "1") (pinfunction "1_1") (pintype "passive"))
      (node (ref "C61") (pin "1") (pinfunction "1_1") (pintype "passive"))
      (node (ref "C74") (pin "1") (pinfunction "1_1") (pintype "passive"))
      (node (ref "C75") (pin "1") (pinfunction "1_1") (pintype "passive"))
      (node (ref "C79") (pin "1") (pinfunction "1_1") (pintype "passive"))
      (node (ref "C87") (pin "1") (pinfunction "1_1") (pintype "passive"))
      (node (ref "C92") (pin "1") (pinfunction "1_1") (pintype "passive"))
      (node (ref "C94") (pin "1") (pinfunction "1_1") (pintype "passive"))
      (node (ref "C96") (pin "1") (pinfunction "1_1") (pintype "passive"))
      (node (ref "L3") (pin "2") (pinfunction "2_2") (pintype "passive"))
      (node (ref "L8") (pin "2") (pinfunction "2_2") (pintype "passive"))
      (node (ref "L9") (pin "2") (pinfunction "2_2") (pintype "passive"))
      (node (ref "U4") (pin "A13") (pinfunction "VCCO_MIO1_501_A13") (pintype "power_in"))
      (node (ref "U4") (pin "B16") (pinfunction "VCCO_MIO1_501_B16") (pintype "power_in"))
      (node (ref "U4") (pin "D12") (pinfunction "VCCO_MIO1_501_D12") (pintype "power_in"))
      (node (ref "U4") (pin "E15") (pinfunction "VCCO_MIO1_501_E15") (pintype "power_in"))
      (node (ref "U4") (pin "F8") (pinfunction "VCCPAUX_F8") (pintype "power_in"))
      (node (ref "U4") (pin "G9") (pinfunction "VCCPAUX_G9") (pintype "power_in"))
      (node (ref "U4") (pin "H8") (pinfunction "VCCPAUX_H8") (pintype "power_in"))
      (node (ref "U4") (pin "J11") (pinfunction "VCCAUX_J11") (pintype "power_in"))
      (node (ref "U4") (pin "K8") (pinfunction "VCCPAUX_K8") (pintype "power_in"))
      (node (ref "U4") (pin "L11") (pinfunction "VCCAUX_L11") (pintype "power_in"))
      (node (ref "U4") (pin "M8") (pinfunction "VCCPAUX_M8") (pintype "power_in"))
      (node (ref "U4") (pin "N11") (pinfunction "VCCAUX_N11") (pintype "power_in"))
      (node (ref "U4") (pin "N9") (pinfunction "VCCAUX_N9") (pintype "power_in"))
      (node (ref "U4") (pin "P10") (pinfunction "VCCAUX_P10") (pintype "power_in"))
      (node (ref "U4") (pin "R9") (pinfunction "VCCAUX_R9") (pintype "power_in"))
    )
    (net (code "15") (name "VCC3.3") (class "Default")
      (node (ref "R28") (pin "1") (pinfunction "1_1") (pintype "passive"))
      (node (ref "R49") (pin "1") (pinfunction "1_1") (pintype "passive"))
      (node (ref "R53") (pin "1") (pinfunction "1_1") (pintype "passive"))
    )
    (net (code "16") (name "VCC3.3_IO") (class "Default")
      (node (ref "C101") (pin "1") (pinfunction "1_1") (pintype "passive"))
      (node (ref "C102") (pin "1") (pinfunction "1_1") (pintype "passive"))
      (node (ref "C103") (pin "1") (pinfunction "1_1") (pintype "passive"))
      (node (ref "C104") (pin "1") (pinfunction "1_1") (pintype "passive"))
      (node (ref "C105") (pin "1") (pinfunction "1_1") (pintype "passive"))
      (node (ref "C108") (pin "1") (pinfunction "1_1") (pintype "passive"))
      (node (ref "C14") (pin "1") (pinfunction "1_1") (pintype "passive"))
      (node (ref "C18") (pin "1") (pinfunction "1_1") (pintype "passive"))
      (node (ref "C21") (pin "1") (pinfunction "1_1") (pintype "passive"))
      (node (ref "C22") (pin "1") (pinfunction "1_1") (pintype "passive"))
      (node (ref "C65") (pin "1") (pinfunction "1_1") (pintype "passive"))
      (node (ref "C69") (pin "1") (pinfunction "1_1") (pintype "passive"))
      (node (ref "C70") (pin "1") (pinfunction "1_1") (pintype "passive"))
      (node (ref "C71") (pin "1") (pinfunction "1_1") (pintype "passive"))
      (node (ref "C72") (pin "1") (pinfunction "1_1") (pintype "passive"))
      (node (ref "C73") (pin "1") (pinfunction "1_1") (pintype "passive"))
      (node (ref "C76") (pin "1") (pinfunction "1_1") (pintype "passive"))
      (node (ref "C77") (pin "1") (pinfunction "1_1") (pintype "passive"))
      (node (ref "C78") (pin "1") (pinfunction "1_1") (pintype "passive"))
      (node (ref "C80") (pin "1") (pinfunction "1_1") (pintype "passive"))
      (node (ref "C86") (pin "1") (pinfunction "1_1") (pintype "passive"))
      (node (ref "C89") (pin "1") (pinfunction "1_1") (pintype "passive"))
      (node (ref "C97") (pin "1") (pinfunction "1_1") (pintype "passive"))
      (node (ref "R79") (pin "2") (pinfunction "2_2") (pintype "passive"))
      (node (ref "R80") (pin "2") (pinfunction "2_2") (pintype "passive"))
      (node (ref "R82") (pin "2") (pinfunction "2_2") (pintype "passive"))
      (node (ref "U4") (pin "B6") (pinfunction "VCCO_MIO0_500_B6") (pintype "power_in"))
      (node (ref "U4") (pin "C19") (pinfunction "VCCO_35_C19") (pintype "power_in"))
      (node (ref "U4") (pin "D7") (pinfunction "VCCO_MIO0_500_D7") (pintype "power_in"))
      (node (ref "U4") (pin "F18") (pinfunction "VCCO_35_F18") (pintype "power_in"))
      (node (ref "U4") (pin "H14") (pinfunction "VCCO_35_H14") (pintype "power_in"))
      (node (ref "U4") (pin "J17") (pinfunction "VCCO_35_J17") (pintype "power_in"))
      (node (ref "U4") (pin "K20") (pinfunction "VCCO_35_K20") (pintype "power_in"))
      (node (ref "U4") (pin "K6") (pinfunction "VCCO_0_K6") (pintype "power_in"))
      (node (ref "U4") (pin "M16") (pinfunction "VCCO_35_M16") (pintype "power_in"))
      (node (ref "U4") (pin "M6") (pinfunction "CFGBVS_0_M6") (pintype "input"))
      (node (ref "U4") (pin "N19") (pinfunction "VCCO_34_N19") (pintype "power_in"))
      (node (ref "U4") (pin "N6") (pinfunction "RSVDVCC3_N6") (pintype "power_in"))
      (node (ref "U4") (pin "R15") (pinfunction "VCCO_34_R15") (pintype "power_in"))
      (node (ref "U4") (pin "R6") (pinfunction "RSVDVCC2_R6") (pintype "power_in"))
      (node (ref "U4") (pin "T18") (pinfunction "VCCO_34_T18") (pintype "power_in"))
      (node (ref "U4") (pin "T6") (pinfunction "RSVDVCC1_T6") (pintype "power_in"))
      (node (ref "U4") (pin "T8") (pinfunction "VCCO_13_T8") (pintype "power_in"))
      (node (ref "U4") (pin "U11") (pinfunction "VCCO_13_U11") (pintype "power_in"))
      (node (ref "U4") (pin "V14") (pinfunction "VCCO_34_V14") (pintype "power_in"))
      (node (ref "U4") (pin "W17") (pinfunction "VCCO_34_W17") (pintype "power_in"))
      (node (ref "U4") (pin "W7") (pinfunction "VCCO_13_W7") (pintype "power_in"))
      (node (ref "U4") (pin "Y10") (pinfunction "VCCO_13_Y10") (pintype "power_in"))
      (node (ref "U4") (pin "Y20") (pinfunction "VCCO_34_Y20") (pintype "power_in"))
    )
    (net (code "17") (name "unconnected-(U4D-DXN_0-PadM10)") (class "Default")
      (node (ref "U4") (pin "M10") (pinfunction "DXN_0_M10") (pintype "input+no_connect"))
    )
    (net (code "18") (name "unconnected-(U4D-DXP_0-PadM9)") (class "Default")
      (node (ref "U4") (pin "M9") (pinfunction "DXP_0_M9") (pintype "input+no_connect"))
    )
  )
)
